# 05_iMX_8X_PCIE.net
KiCad netlist of a schematic drawn in Altium Designer
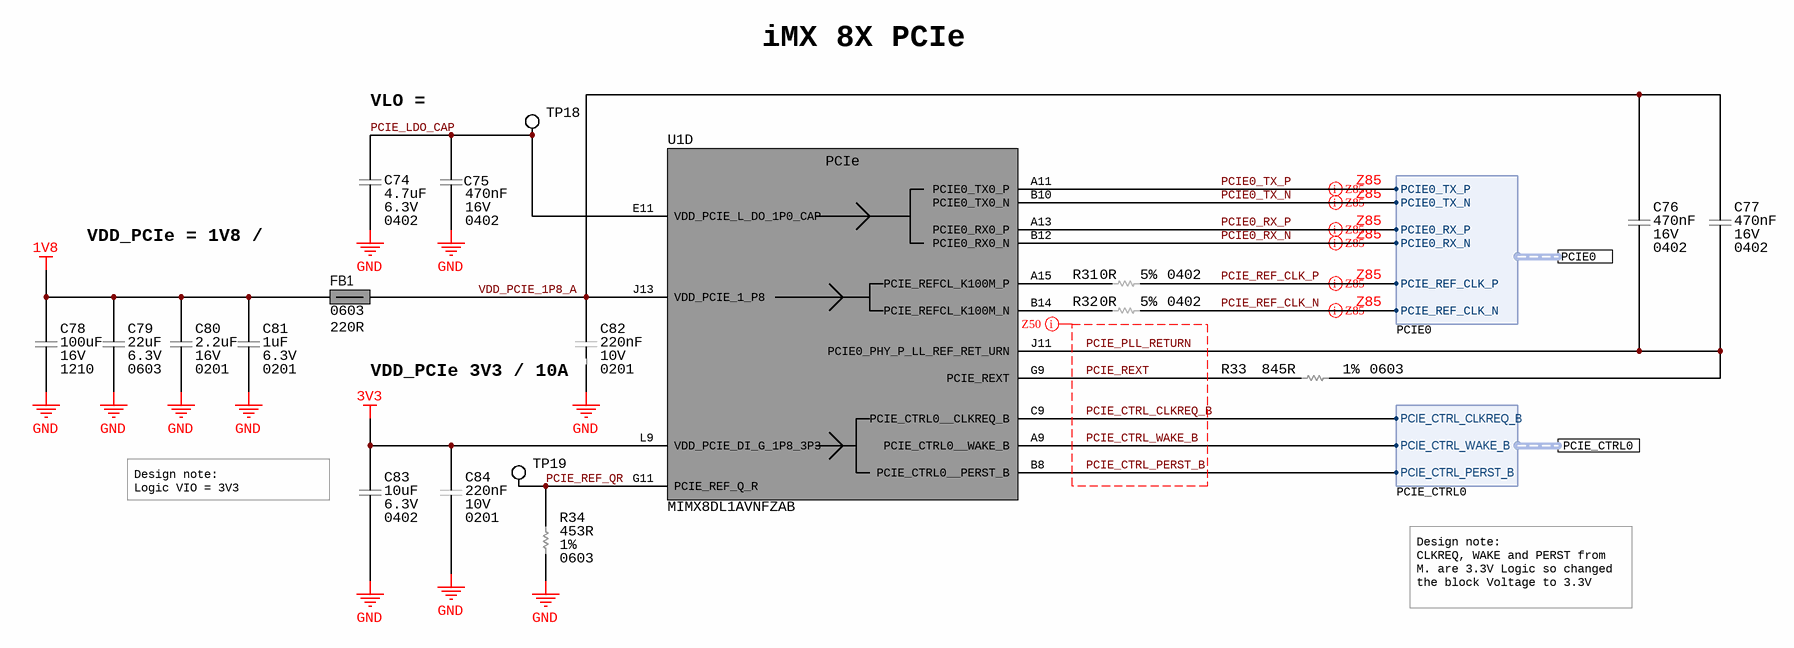
[diagram p0: 05_iMX 8X_PCIE.SchDoc]

(export (version "E")
  (design (tool "Eeschema 10.0.6"))
  (components
    (comp (ref "C74")
      (value "C1005X5R0J475M050BC")
      (footprint "CAP_0402_CAPC1005X05N")
      (description "Multilayer Ceramic Capacitor, 4.7 uF, 6.3 V, ± 20%, X5R, 0402 [1005 Metric]")
      (fields
        (field (name "MANUFACTURER") "TDK")
        (field (name "TOLERANCE") "20%")
        (field (name "CAPACITANCE") "4.7uF")
        (field (name "VOLTAGE RATING") "6.3V")
        (field (name "CASE/PACKAGE") "0402")
      )
      (libsource (lib "Electronic Devices_LIB") (part "CAP_4.7UF_6.3V_X5R_0402"))
    )
    (comp (ref "C75")
      (value "GRT155R61C474KE01D")
      (footprint "CAP_0402_CAPC1005X05N")
      (description "0402 0.47 uF 16 V ±10 % Tolerance X5R SMT Multilayer Ceramic Capacitor")
      (fields
        (field (name "MANUFACTURER") "Murata")
        (field (name "TOLERANCE") "10%")
        (field (name "VOLTAGE RATING") "16V")
        (field (name "CAPACITANCE") "470nF")
        (field (name "CASE/PACKAGE") "0402")
      )
      (libsource (lib "Electronic Devices_LIB") (part "CAP_0.47UF_16V_X5R_0402"))
    )
    (comp (ref "C76")
      (value "GRT155R61C474KE01D")
      (footprint "CAP_0402_CAPC1005X05N")
      (description "0402 0.47 uF 16 V ±10 % Tolerance X5R SMT Multilayer Ceramic Capacitor")
      (fields
        (field (name "MANUFACTURER") "Murata")
        (field (name "TOLERANCE") "10%")
        (field (name "VOLTAGE RATING") "16V")
        (field (name "CAPACITANCE") "470nF")
        (field (name "CASE/PACKAGE") "0402")
      )
      (libsource (lib "Electronic Devices_LIB") (part "CAP_0.47UF_16V_X5R_0402"))
    )
    (comp (ref "C77")
      (value "GRT155R61C474KE01D")
      (footprint "CAP_0402_CAPC1005X05N")
      (description "0402 0.47 uF 16 V ±10 % Tolerance X5R SMT Multilayer Ceramic Capacitor")
      (fields
        (field (name "MANUFACTURER") "Murata")
        (field (name "TOLERANCE") "10%")
        (field (name "VOLTAGE RATING") "16V")
        (field (name "CAPACITANCE") "470nF")
        (field (name "CASE/PACKAGE") "0402")
      )
      (libsource (lib "Electronic Devices_LIB") (part "CAP_0.47UF_16V_X5R_0402"))
    )
    (comp (ref "C78")
      (value "EMK325ABJ107MM-T")
      (footprint "CAP_1210_CAPC3225X270N")
      (description "Multilayer Ceramic Capacitor, 100 uF, 16 V, ± 20%, X5R, 1210 [3225 Metric]")
      (fields
        (field (name "MANUFACTURER") "Taiyo Yuden")
        (field (name "TOLERANCE") "20%")
        (field (name "VOLTAGE RATING") "16V")
        (field (name "CAPACITANCE") "100uF")
        (field (name "CASE/PACKAGE") "1210")
      )
      (libsource (lib "Electronic Devices_LIB") (part "CAP_100UF_16V_X5R_1210"))
    )
    (comp (ref "C79")
      (value "GRM188R60J226MEA0D")
      (footprint "CAP_0603_CAPC1608X08N")
      (description "Multilayer Ceramic Capacitor, 22 uF, 6.3 V, ï¿½ 20%, X5R, 0603 [1608 Metric]")
      (fields
        (field (name "MANUFACTURER") "Murata")
        (field (name "TOLERANCE") "20%")
        (field (name "VOLTAGE RATING") "6.3V")
        (field (name "CAPACITANCE") "22uF")
        (field (name "CASE/PACKAGE") "0603")
      )
      (libsource (lib "Electronic Devices_LIB") (part "CAP_22uF_6.3V_X5R_0603"))
    )
    (comp (ref "C80")
      (value "GRM035R61C225ME01D")
      (footprint "CAP_0201_CAPC0603X03N")
      (description "General Up to 85C Reflow soldering")
      (fields
        (field (name "MANUFACTURER") "Murata")
        (field (name "TOLERANCE") "20%")
        (field (name "CAPACITANCE") "2.2uF")
        (field (name "VOLTAGE RATING") "16V")
        (field (name "CASE/PACKAGE") "0201")
      )
      (libsource (lib "Electronic Devices_LIB") (part "CAP_2.2uF_16V_X5R_0201"))
    )
    (comp (ref "C81")
      (value "02016D105MAT2A")
      (footprint "CAP_0201_CAPC0603X03N")
      (description "0201 1 uF 6.3 V ±20 % Tolerance X5R Surface Mount Multilayer Ceramic Capacitor")
      (fields
        (field (name "MANUFACTURER") "Kyocera AVX")
        (field (name "TOLERANCE") "20%")
        (field (name "VOLTAGE RATING (DC)") "6.3V")
        (field (name "CAPACITANCE") "1uF")
        (field (name "CASE/PACKAGE") "0201")
      )
      (libsource (lib "Electronic Devices_LIB") (part "CAP_1UF_6.3V_X5R_0201"))
    )
    (comp (ref "C82")
      (value "LMK063BJ224MP-F")
      (footprint "CAP_0201_CAPC0603X03N")
      (description "Multilayer Ceramic Capacitors (High dielectric type), 10V, 0.22 uF, ± 20 %, 0201, X5R, RoHS")
      (fields
        (field (name "MANUFACTURER") "Taiyo Yuden")
        (field (name "TOLERANCE") "20%")
        (field (name "VOLTAGE RATING (DC)") "10V")
        (field (name "CAPACITANCE") "220nF")
        (field (name "CASE/PACKAGE") "0201")
      )
      (libsource (lib "Electronic Devices_LIB") (part "CAP_0.22UF_10V_X5R_0201"))
    )
    (comp (ref "C83")
      (value "CL05A106MQ5NUNC")
      (footprint "CAP_0402_CAPC1005X05N")
      (description "Cap Ceramic 10uF 6.3V X5R 20% SMD 0402 85C T/R")
      (fields
        (field (name "MANUFACTURER") "Samsung")
        (field (name "TOLERANCE") "20%")
        (field (name "CASE/PACKAGE") "0402")
        (field (name "CAPACITANCE") "10uF")
        (field (name "VOLTAGE RATING") "6.3V")
      )
      (libsource (lib "Electronic Devices_LIB") (part "CAP_10UF_6.3V_X5R_0402"))
    )
    (comp (ref "C84")
      (value "LMK063BJ224MP-F")
      (footprint "CAP_0201_CAPC0603X03N")
      (description "Multilayer Ceramic Capacitors (High dielectric type), 10V, 0.22 uF, ± 20 %, 0201, X5R, RoHS")
      (fields
        (field (name "MANUFACTURER") "Taiyo Yuden")
        (field (name "TOLERANCE") "20%")
        (field (name "VOLTAGE RATING (DC)") "10V")
        (field (name "CAPACITANCE") "220nF")
        (field (name "CASE/PACKAGE") "0201")
      )
      (libsource (lib "Electronic Devices_LIB") (part "CAP_0.22UF_10V_X5R_0201"))
    )
    (comp (ref "FB1")
      (value "BLM18SG221TN1D")
      (footprint "IND_0603_INDC1608X08N")
      (description "Ferrite Beads Multi-Layer 220Ohm 25% 100MHz 2.5A 40mOhm DCR 0603 Paper T/R")
      (fields
        (field (name "MANUFACTURER") "Murata")
        (field (name "TOLERANCE") "25%")
        (field (name "CASE/PACKAGE") "0603")
        (field (name "IMPEDANCE") "220R")
      )
      (libsource (lib "Electronic Devices_LIB") (part "IND_FERRITE_BEADS_220R_2.5A_BLM18SG221TN1D"))
    )
    (comp (ref "R31")
      (value "ERJ-2GE0R00X")
      (footprint "RES_0402_RESC1005X04N")
      (description "SMD Chip Resistor, Jumper, 0 ohm, 100 mW, 0402 [1005 Metric], Thick Film, General Purpose")
      (fields
        (field (name "MANUFACTURER") "Panasonic")
        (field (name "CASE CODE (IMPERIAL)") "0402")
        (field (name "TOLERANCE") "5%")
        (field (name "RESISTANCE") "0R")
      )
      (libsource (lib "Electronic Devices_LIB") (part "RES_0R_5%_100mW_0402"))
    )
    (comp (ref "R32")
      (value "ERJ-2GE0R00X")
      (footprint "RES_0402_RESC1005X04N")
      (description "SMD Chip Resistor, Jumper, 0 ohm, 100 mW, 0402 [1005 Metric], Thick Film, General Purpose")
      (fields
        (field (name "MANUFACTURER") "Panasonic")
        (field (name "CASE CODE (IMPERIAL)") "0402")
        (field (name "TOLERANCE") "5%")
        (field (name "RESISTANCE") "0R")
      )
      (libsource (lib "Electronic Devices_LIB") (part "RES_0R_5%_100mW_0402"))
    )
    (comp (ref "R33")
      (value "RC0603FR-07845RL")
      (footprint "RES_0603_RESC1608X04N")
      (description "SMD Chip Resistor, 845 Ohm, ± 1%, 100 mW, 0603 [1608 Metric], Thick Film, General Purpose")
      (fields
        (field (name "MANUFACTURER") "Yageo")
        (field (name "TOLERANCE") "1%")
        (field (name "RESISTANCE") "845R")
        (field (name "CASE/PACKAGE") "0603")
      )
      (libsource (lib "Electronic Devices_LIB") (part "RES_845R_1%_100mW_0603"))
    )
    (comp (ref "R34")
      (value "CRCW0603453RFKEA")
      (footprint "RES_0603_RESC1608X04N")
      (description "Res Thick Film 0603 453 Ohm 1% 0.1W(1/10W) ±100ppm/C Pad SMD T/R Automotive AEC-Q200")
      (fields
        (field (name "MANUFACTURER") "Vishay")
        (field (name "TOLERANCE") "1%")
        (field (name "RESISTANCE") "453R")
        (field (name "RESISTANCE TOLERANCE") "1%")
        (field (name "CASE/PACKAGE") "0603")
      )
      (libsource (lib "Electronic Devices_LIB") (part "RES_453R_1%_100mW_0603"))
    )
    (comp (ref "TP18")
      (value "NO COMPONENT")
      (footprint "TP_PAD_0.5MM_SMD_ROUND")
      (description "Test Point, SMD pad, round, 1.5mm, 1.6mm, 3mm diameter")
      (libsource (lib "Electronic Devices_LIB") (part "TP_PAD_SMD_SMALL"))
    )
    (comp (ref "TP19")
      (value "NO COMPONENT")
      (footprint "TP_PAD_0.5MM_SMD_ROUND")
      (description "Test Point, SMD pad, round, 1.5mm, 1.6mm, 3mm diameter")
      (libsource (lib "Electronic Devices_LIB") (part "TP_PAD_SMD_SMALL"))
    )
    (comp (ref "U1")
      (value "MIMX8DL1AVNFZAB")
      (footprint "MIMX8DL1AVNFZAB")
      (description "I.MX8 Dxl 15SQ / Tray Rohs Compliant: Yes")
      (fields (field (name "MANUFACTURER") "NXP Semiconductors"))
      (libsource (lib "Electronic Devices_LIB") (part "IC_MPU_ARM_1.2GHz_MIMX8DL1AVNFZAB"))
    )
  )
  (nets
    (net (code "3") (name "/PCIE0_RX_N") (class "Default")
      (node (ref "U1") (pin "B12") (pinfunction "PCIE0_RX0_N_B12") (pintype "passive"))
    )
    (net (code "4") (name "/PCIE0_RX_P") (class "Default")
      (node (ref "U1") (pin "A13") (pinfunction "PCIE0_RX0_P_A13") (pintype "passive"))
    )
    (net (code "5") (name "/PCIE0_TX_N") (class "Default")
      (node (ref "U1") (pin "B10") (pinfunction "PCIE0_TX0_N_B10") (pintype "passive"))
    )
    (net (code "6") (name "/PCIE0_TX_P") (class "Default")
      (node (ref "U1") (pin "A11") (pinfunction "PCIE0_TX0_P_A11") (pintype "passive"))
    )
    (net (code "7") (name "/PCIE_CTRL_CLKREQ_B") (class "Default")
      (node (ref "U1") (pin "C9") (pinfunction "PCIE_CTRL0__CLKREQ_B_C9") (pintype "passive"))
    )
    (net (code "8") (name "/PCIE_CTRL_PERST_B") (class "Default")
      (node (ref "U1") (pin "B8") (pinfunction "PCIE_CTRL0__PERST_B_B8") (pintype "passive"))
    )
    (net (code "9") (name "/PCIE_CTRL_WAKE_B") (class "Default")
      (node (ref "U1") (pin "A9") (pinfunction "PCIE_CTRL0__WAKE_B_A9") (pintype "passive"))
    )
    (net (code "10") (name "/PCIE_LDO_CAP") (class "Default")
      (node (ref "C74") (pin "2") (pinfunction "2_2") (pintype "passive"))
      (node (ref "C75") (pin "2") (pinfunction "2_2") (pintype "passive"))
      (node (ref "TP18") (pin "1") (pinfunction "1_1") (pintype "passive"))
      (node (ref "U1") (pin "E11") (pinfunction "VDD_PCIE_L_DO_1P0_CAP_E11") (pintype "passive"))
    )
    (net (code "11") (name "/PCIE_PLL_RETURN") (class "Default")
      (node (ref "C76") (pin "1") (pinfunction "1_1") (pintype "passive"))
      (node (ref "C77") (pin "1") (pinfunction "1_1") (pintype "passive"))
      (node (ref "R33") (pin "2") (pinfunction "2_2") (pintype "passive"))
      (node (ref "U1") (pin "J11") (pinfunction "PCIE0_PHY_P_LL_REF_RET_URN_J11") (pintype "passive"))
    )
    (net (code "12") (name "/PCIE_REF_CLK_N") (class "Default")
      (node (ref "R32") (pin "2") (pinfunction "2_2") (pintype "passive"))
    )
    (net (code "13") (name "/PCIE_REF_CLK_P") (class "Default")
      (node (ref "R31") (pin "2") (pinfunction "2_2") (pintype "passive"))
    )
    (net (code "14") (name "/PCIE_REF_QR") (class "Default")
      (node (ref "R34") (pin "2") (pinfunction "2_2") (pintype "passive"))
      (node (ref "TP19") (pin "1") (pinfunction "1_1") (pintype "passive"))
      (node (ref "U1") (pin "G11") (pinfunction "PCIE_REF_Q_R_G11") (pintype "passive"))
    )
    (net (code "15") (name "/PCIE_REXT") (class "Default")
      (node (ref "R33") (pin "1") (pinfunction "1_1") (pintype "passive"))
      (node (ref "U1") (pin "G9") (pinfunction "PCIE_REXT_G9") (pintype "passive"))
    )
    (net (code "16") (name "/VDD_PCIE_1P8_A") (class "Default")
      (node (ref "C76") (pin "2") (pinfunction "2_2") (pintype "passive"))
      (node (ref "C77") (pin "2") (pinfunction "2_2") (pintype "passive"))
      (node (ref "C82") (pin "2") (pinfunction "2_2") (pintype "passive"))
      (node (ref "FB1") (pin "2") (pinfunction "2_2") (pintype "passive"))
      (node (ref "U1") (pin "J13") (pinfunction "VDD_PCIE_1_P8_J13") (pintype "passive"))
    )
    (net (code "19") (name "1V8") (class "Default")
      (node (ref "C78") (pin "2") (pinfunction "2_2") (pintype "passive"))
      (node (ref "C79") (pin "2") (pinfunction "2_2") (pintype "passive"))
      (node (ref "C80") (pin "2") (pinfunction "2_2") (pintype "passive"))
      (node (ref "C81") (pin "2") (pinfunction "2_2") (pintype "passive"))
      (node (ref "FB1") (pin "1") (pinfunction "1_1") (pintype "passive"))
    )
    (net (code "20") (name "3V3") (class "Default")
      (node (ref "C83") (pin "2") (pinfunction "2_2") (pintype "passive"))
      (node (ref "C84") (pin "2") (pinfunction "2_2") (pintype "passive"))
      (node (ref "U1") (pin "L9") (pinfunction "VDD_PCIE_DI_G_1P8_3P3_L9") (pintype "passive"))
    )
    (net (code "21") (name "GND") (class "Default")
      (node (ref "C74") (pin "1") (pinfunction "1_1") (pintype "passive"))
      (node (ref "C75") (pin "1") (pinfunction "1_1") (pintype "passive"))
      (node (ref "C78") (pin "1") (pinfunction "1_1") (pintype "passive"))
      (node (ref "C79") (pin "1") (pinfunction "1_1") (pintype "passive"))
      (node (ref "C80") (pin "1") (pinfunction "1_1") (pintype "passive"))
      (node (ref "C81") (pin "1") (pinfunction "1_1") (pintype "passive"))
      (node (ref "C82") (pin "1") (pinfunction "1_1") (pintype "passive"))
      (node (ref "C83") (pin "1") (pinfunction "1_1") (pintype "passive"))
      (node (ref "C84") (pin "1") (pinfunction "1_1") (pintype "passive"))
      (node (ref "R34") (pin "1") (pinfunction "1_1") (pintype "passive"))
    )
    (net (code "22") (name "Net-(U1D-PCIE_REFCL_K100M_N)") (class "Default")
      (node (ref "R32") (pin "1") (pinfunction "1_1") (pintype "passive"))
      (node (ref "U1") (pin "B14") (pinfunction "PCIE_REFCL_K100M_N_B14") (pintype "passive"))
    )
    (net (code "23") (name "Net-(U1D-PCIE_REFCL_K100M_P)") (class "Default")
      (node (ref "R31") (pin "1") (pinfunction "1_1") (pintype "passive"))
      (node (ref "U1") (pin "A15") (pinfunction "PCIE_REFCL_K100M_P_A15") (pintype "passive"))
    )
  )
)
